# DualUSB3_0_CON.net
KiCad netlist of a schematic drawn in Altium Designer
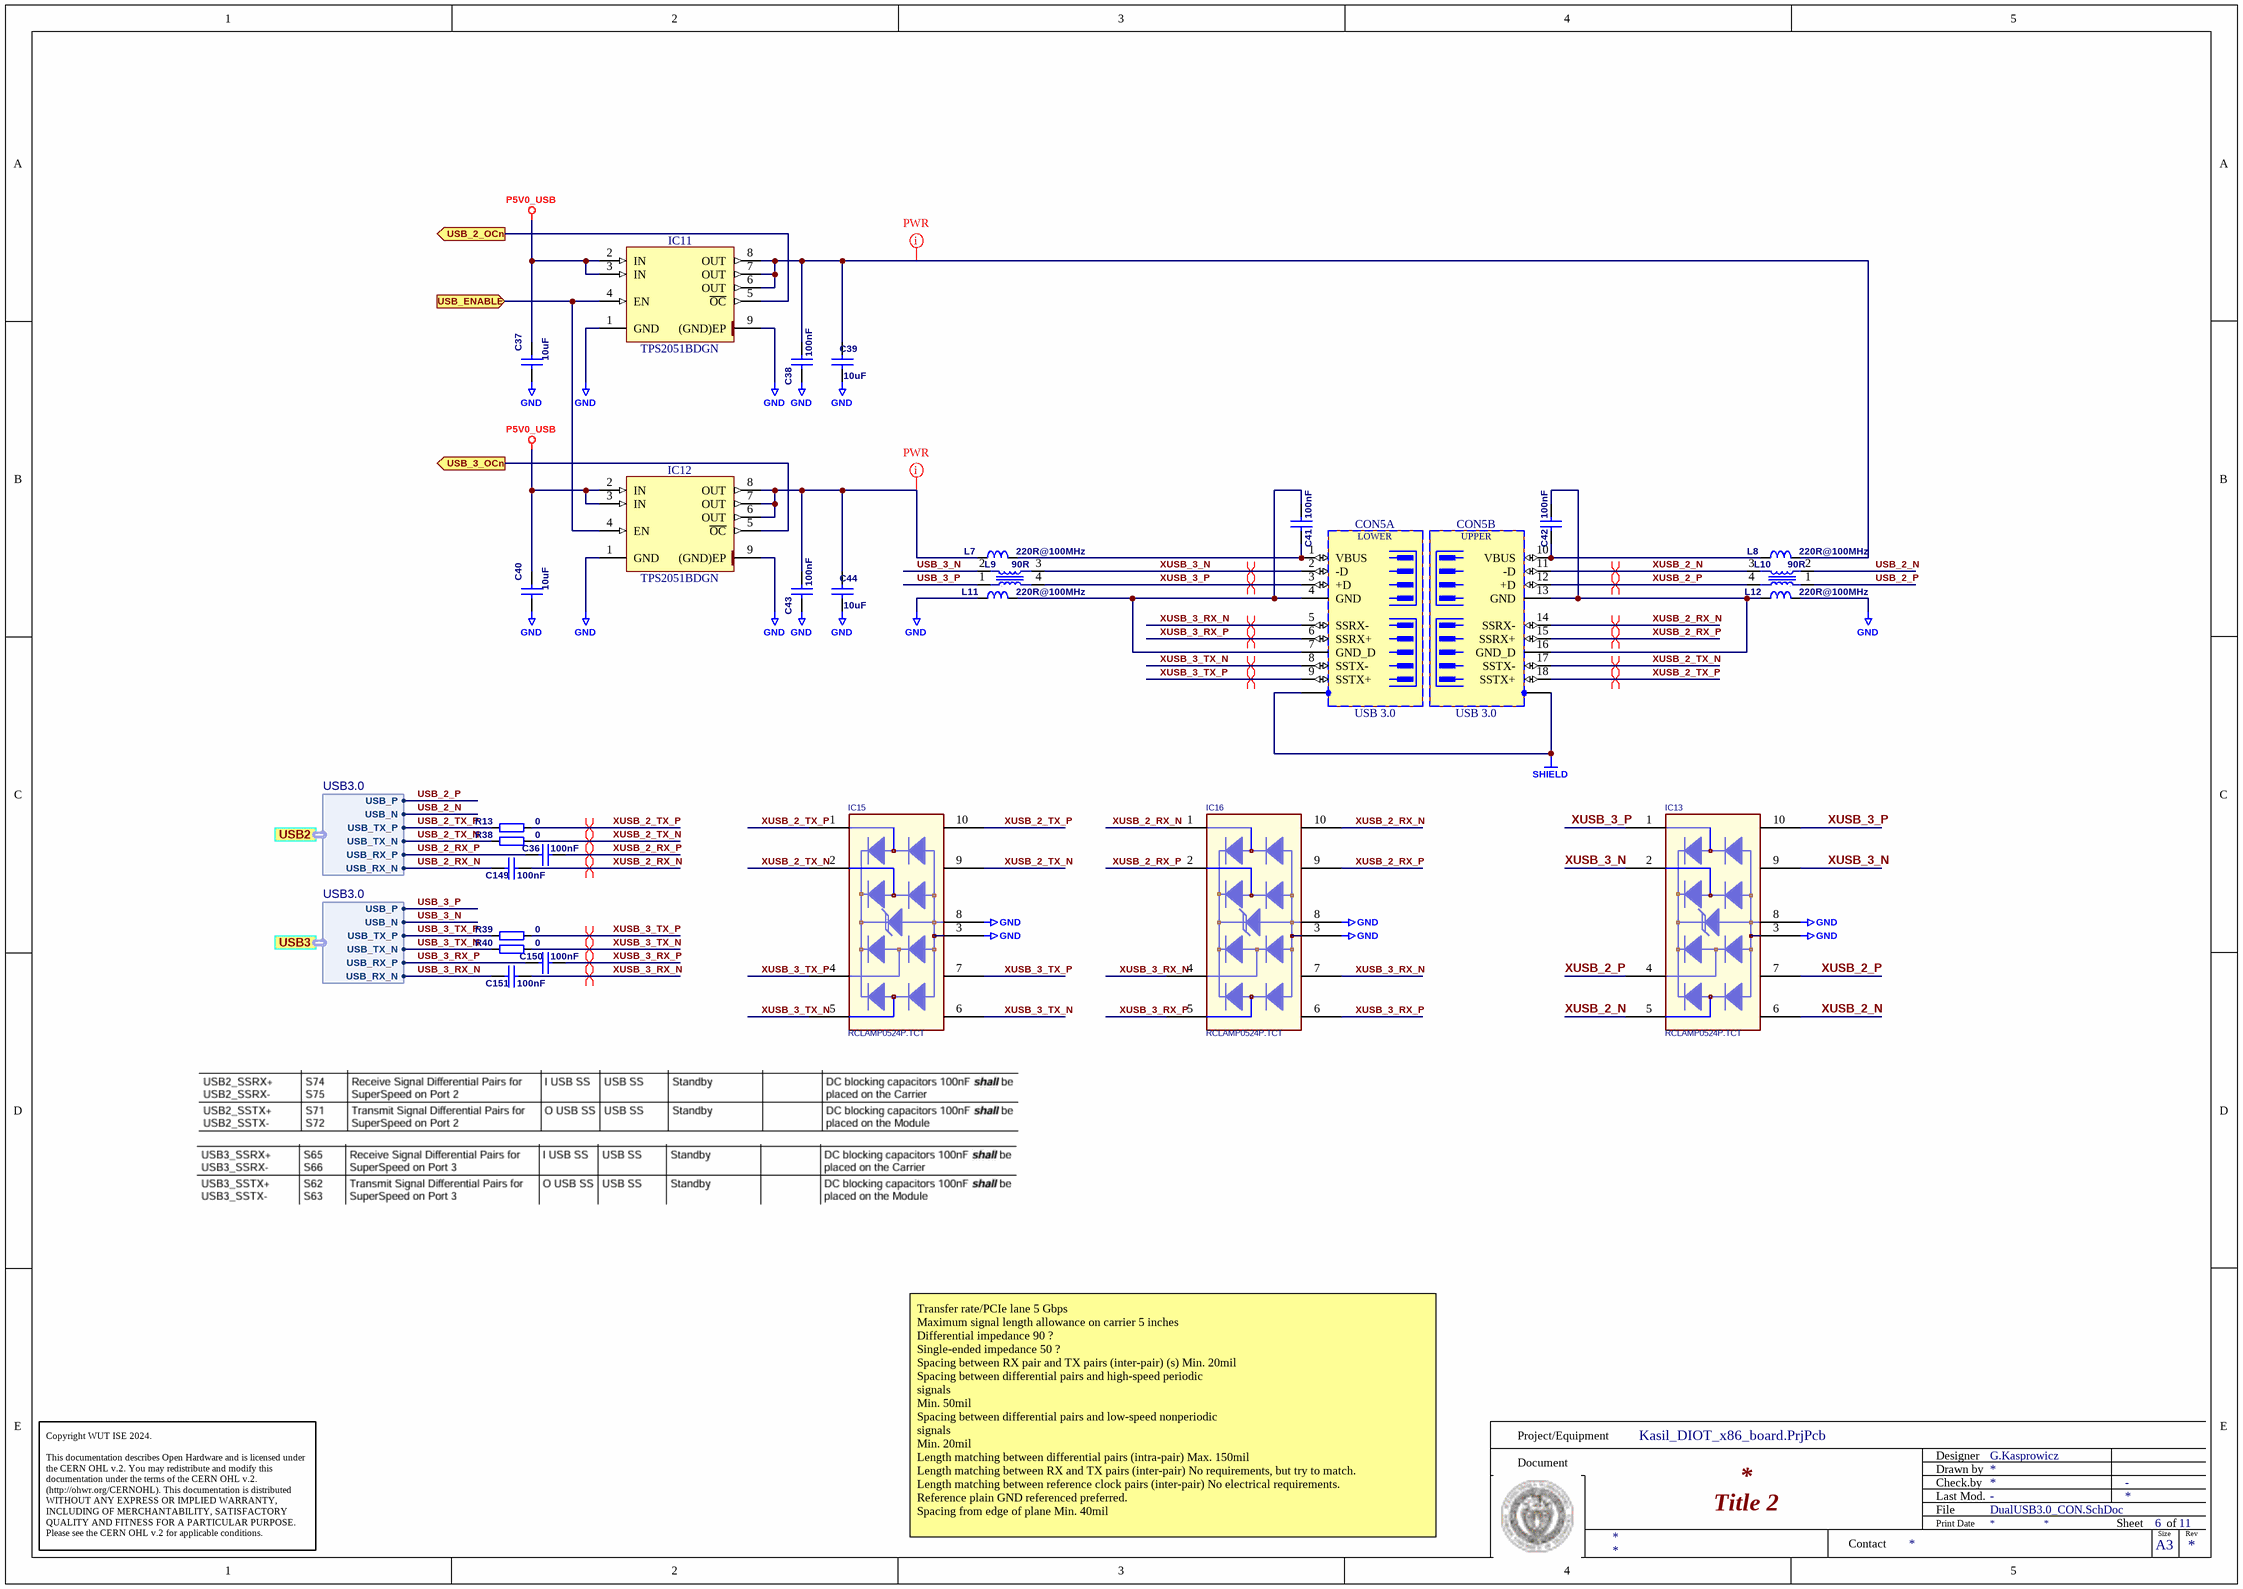
[diagram p0: DualUSB3.0_CON.SchDoc]

(export (version "E")
  (design (tool "Eeschema 10.0.6"))
  (components
    (comp (ref "C36")
      (value "100nF")
      (footprint "CAPC1005X55N")
      (description "Non-polarised capacitor")
      (fields
        (field (name "PART NUMBER") "CC0402_100NF_16V_10%_X7R")
        (field (name "VOLTAGE") "16V")
        (field (name "AUTHOR") "CERN DEM JLC")
      )
      (libsource (lib "Capacitors") (part "Capacitor - non polarized"))
    )
    (comp (ref "C37")
      (value "10uF")
      (footprint "CAPC2012X135N")
      (description "Non-polarised capacitor")
      (fields
        (field (name "PART NUMBER") "CC0805_10UF_10V_10%_X7R")
        (field (name "VOLTAGE") "10V")
        (field (name "AUTHOR") "CERN DEM JLC")
      )
      (libsource (lib "Capacitors") (part "Capacitor - non polarized"))
    )
    (comp (ref "C38")
      (value "100nF")
      (footprint "CAPC1005X55N")
      (description "Non-polarised capacitor")
      (fields
        (field (name "PART NUMBER") "CC0402_100NF_16V_10%_X7R")
        (field (name "VOLTAGE") "16V")
        (field (name "AUTHOR") "CERN DEM JLC")
      )
      (libsource (lib "Capacitors") (part "Capacitor - non polarized"))
    )
    (comp (ref "C39")
      (value "10uF")
      (footprint "CAPC2012X135N")
      (description "Non-polarised capacitor")
      (fields
        (field (name "PART NUMBER") "CC0805_10UF_10V_10%_X7R")
        (field (name "VOLTAGE") "10V")
        (field (name "AUTHOR") "CERN DEM JLC")
      )
      (libsource (lib "Capacitors") (part "Capacitor - non polarized"))
    )
    (comp (ref "C40")
      (value "10uF")
      (footprint "CAPC2012X135N")
      (description "Non-polarised capacitor")
      (fields
        (field (name "PART NUMBER") "CC0805_10UF_10V_10%_X7R")
        (field (name "VOLTAGE") "10V")
        (field (name "AUTHOR") "CERN DEM JLC")
      )
      (libsource (lib "Capacitors") (part "Capacitor - non polarized"))
    )
    (comp (ref "C41")
      (value "100nF")
      (footprint "CAPC1005X55N")
      (description "Non-polarised capacitor")
      (fields
        (field (name "PART NUMBER") "CC0402_100NF_16V_10%_X7R")
        (field (name "VOLTAGE") "16V")
        (field (name "AUTHOR") "CERN DEM JLC")
      )
      (libsource (lib "Capacitors") (part "Capacitor - non polarized"))
    )
    (comp (ref "C42")
      (value "100nF")
      (footprint "CAPC1005X55N")
      (description "Non-polarised capacitor")
      (fields
        (field (name "PART NUMBER") "CC0402_100NF_16V_10%_X7R")
        (field (name "VOLTAGE") "16V")
        (field (name "AUTHOR") "CERN DEM JLC")
      )
      (libsource (lib "Capacitors") (part "Capacitor - non polarized"))
    )
    (comp (ref "C43")
      (value "100nF")
      (footprint "CAPC1005X55N")
      (description "Non-polarised capacitor")
      (fields
        (field (name "PART NUMBER") "CC0402_100NF_16V_10%_X7R")
        (field (name "VOLTAGE") "16V")
        (field (name "AUTHOR") "CERN DEM JLC")
      )
      (libsource (lib "Capacitors") (part "Capacitor - non polarized"))
    )
    (comp (ref "C44")
      (value "10uF")
      (footprint "CAPC2012X135N")
      (description "Non-polarised capacitor")
      (fields
        (field (name "PART NUMBER") "CC0805_10UF_10V_10%_X7R")
        (field (name "VOLTAGE") "10V")
        (field (name "AUTHOR") "CERN DEM JLC")
      )
      (libsource (lib "Capacitors") (part "Capacitor - non polarized"))
    )
    (comp (ref "C149")
      (value "100nF")
      (footprint "CAPC1005X55N")
      (description "Non-polarised capacitor")
      (fields
        (field (name "PART NUMBER") "CC0402_100NF_16V_10%_X7R")
        (field (name "VOLTAGE") "16V")
        (field (name "AUTHOR") "CERN DEM JLC")
      )
      (libsource (lib "Capacitors") (part "Capacitor - non polarized"))
    )
    (comp (ref "C150")
      (value "100nF")
      (footprint "CAPC1005X55N")
      (description "Non-polarised capacitor")
      (fields
        (field (name "PART NUMBER") "CC0402_100NF_16V_10%_X7R")
        (field (name "VOLTAGE") "16V")
        (field (name "AUTHOR") "CERN DEM JLC")
      )
      (libsource (lib "Capacitors") (part "Capacitor - non polarized"))
    )
    (comp (ref "C151")
      (value "100nF")
      (footprint "CAPC1005X55N")
      (description "Non-polarised capacitor")
      (fields
        (field (name "PART NUMBER") "CC0402_100NF_16V_10%_X7R")
        (field (name "VOLTAGE") "16V")
        (field (name "AUTHOR") "CERN DEM JLC")
      )
      (libsource (lib "Capacitors") (part "Capacitor - non polarized"))
    )
    (comp (ref "CON5")
      (value "USB 3.0")
      (footprint "WURTH_692141030100")
      (description "2x9 Pin + 1 Shield  Duals USB 3.0 Type A Receptacle")
      (fields
        (field (name "PART NUMBER") "WURTH_692141030100")
        (field (name "MANUFACTURER") "WURTH ELEKTRONIK")
        (field (name "AUTHOR") "CERN DEM JLC")
      )
      (libsource (lib "") (part "Connector USB3 x2 Type A - 18 Pin + 1 Shield_1"))
    )
    (comp (ref "IC11")
      (value "TPS2051BDGN")
      (footprint "SOP65P490X110-9N-R157X189")
      (description "One Channel, Current-Limited, Power-Distribution Switches")
      (fields (field (name "MANUFACTURER") "TEXAS INSTRUMENTS") (field (name "AUTHOR") "CERN DEM BC"))
      (libsource (lib "ICs And Semiconductors") (part "TPS2051BDGN"))
    )
    (comp (ref "IC12")
      (value "TPS2051BDGN")
      (footprint "SOP65P490X110-9N-R157X189")
      (description "One Channel, Current-Limited, Power-Distribution Switches")
      (fields (field (name "MANUFACTURER") "TEXAS INSTRUMENTS") (field (name "AUTHOR") "CERN DEM BC"))
      (libsource (lib "ICs And Semiconductors") (part "TPS2051BDGN"))
    )
    (comp (ref "IC13")
      (value "RCLAMP0524P.TCT")
      (description "DIODE,RCLAMP0524P,SEMTECH")
      (libsource (lib "LIBRARY_SCH") (part "D_TVS_RCLAMP0524P"))
    )
    (comp (ref "IC15")
      (value "RCLAMP0524P.TCT")
      (description "DIODE,RCLAMP0524P,SEMTECH")
      (libsource (lib "LIBRARY_SCH") (part "D_TVS_RCLAMP0524P"))
    )
    (comp (ref "IC16")
      (value "RCLAMP0524P.TCT")
      (description "DIODE,RCLAMP0524P,SEMTECH")
      (libsource (lib "LIBRARY_SCH") (part "D_TVS_RCLAMP0524P"))
    )
    (comp (ref "L7")
      (value "220R@100MHz")
      (footprint "INDC2012X105N")
      (description "Inductor")
      (fields
        (field (name "PART NUMBER") "IND0805_MURATA_BLM21PG221SN1D")
        (field (name "POWER") "2A")
        (field (name "AUTHOR") "CERN DEM JLC")
      )
      (libsource (lib "Inductors & Transformers") (part "Inductor"))
    )
    (comp (ref "L8")
      (value "220R@100MHz")
      (footprint "INDC2012X105N")
      (description "Inductor")
      (fields
        (field (name "PART NUMBER") "IND0805_MURATA_BLM21PG221SN1D")
        (field (name "POWER") "2A")
        (field (name "AUTHOR") "CERN DEM JLC")
      )
      (libsource (lib "Inductors & Transformers") (part "Inductor"))
    )
    (comp (ref "L9")
      (value "90R")
      (footprint "DLSCM0805")
      (description "Common Mode Choke 90R")
      (fields (field (name "Comment") "DLSCM0805-900M or DLW21SN900SQ2L"))
      (libsource (lib "") (part "L_CMC_DLSCM0805_90R_1"))
    )
    (comp (ref "L10")
      (value "90R")
      (footprint "DLSCM0805")
      (description "Common Mode Choke 90R")
      (fields (field (name "Comment") "DLSCM0805-900M or DLW21SN900SQ2L"))
      (libsource (lib "LIBRARY_SCH") (part "L_CMC_DLSCM0805_90R"))
    )
    (comp (ref "L11")
      (value "220R@100MHz")
      (footprint "INDC2012X105N")
      (description "Inductor")
      (fields
        (field (name "PART NUMBER") "IND0805_MURATA_BLM21PG221SN1D")
        (field (name "POWER") "2A")
        (field (name "AUTHOR") "CERN DEM JLC")
      )
      (libsource (lib "Inductors & Transformers") (part "Inductor"))
    )
    (comp (ref "L12")
      (value "220R@100MHz")
      (footprint "INDC2012X105N")
      (description "Inductor")
      (fields
        (field (name "PART NUMBER") "IND0805_MURATA_BLM21PG221SN1D")
        (field (name "POWER") "2A")
        (field (name "AUTHOR") "CERN DEM JLC")
      )
      (libsource (lib "Inductors & Transformers") (part "Inductor"))
    )
    (comp (ref "R13")
      (value "0")
      (footprint "RESC1005X40N")
      (description "Resistor")
      (fields
        (field (name "PART NUMBER") "R0402_0R_JUMPER")
        (field (name "MANUFACTURER") "GENERIC")
        (field (name "AUTHOR") "CERN DEM JLC")
      )
      (libsource (lib "Resistors") (part "Resistor"))
    )
    (comp (ref "R38")
      (value "0")
      (footprint "RESC1005X40N")
      (description "Resistor")
      (fields
        (field (name "PART NUMBER") "R0402_0R_JUMPER")
        (field (name "MANUFACTURER") "GENERIC")
        (field (name "AUTHOR") "CERN DEM JLC")
      )
      (libsource (lib "Resistors") (part "Resistor"))
    )
    (comp (ref "R39")
      (value "0")
      (footprint "RESC1005X40N")
      (description "Resistor")
      (fields
        (field (name "PART NUMBER") "R0402_0R_JUMPER")
        (field (name "MANUFACTURER") "GENERIC")
        (field (name "AUTHOR") "CERN DEM JLC")
      )
      (libsource (lib "Resistors") (part "Resistor"))
    )
    (comp (ref "R40")
      (value "0")
      (footprint "RESC1005X40N")
      (description "Resistor")
      (fields
        (field (name "PART NUMBER") "R0402_0R_JUMPER")
        (field (name "MANUFACTURER") "GENERIC")
        (field (name "AUTHOR") "CERN DEM JLC")
      )
      (libsource (lib "Resistors") (part "Resistor"))
    )
  )
  (nets
    (net (code "2") (name "/USB_2_N") (class "Default")
      (node (ref "L10") (pin "2") (pinfunction "2_2") (pintype "passive"))
    )
    (net (code "3") (name "/USB_2_OCn") (class "Default")
      (node (ref "IC11") (pin "5") (pinfunction "~{OC}_5") (pintype "output"))
    )
    (net (code "4") (name "/USB_2_P") (class "Default")
      (node (ref "L10") (pin "1") (pinfunction "1_1") (pintype "passive"))
    )
    (net (code "5") (name "/USB_2_RX_N") (class "Default")
      (node (ref "C149") (pin "1") (pinfunction "1_1") (pintype "passive"))
    )
    (net (code "6") (name "/USB_2_RX_P") (class "Default")
      (node (ref "C36") (pin "1") (pinfunction "1_1") (pintype "passive"))
    )
    (net (code "7") (name "/USB_2_TX_N") (class "Default")
      (node (ref "R38") (pin "1") (pinfunction "1_1") (pintype "passive"))
    )
    (net (code "8") (name "/USB_2_TX_P") (class "Default")
      (node (ref "R13") (pin "1") (pinfunction "1_1") (pintype "passive"))
    )
    (net (code "9") (name "/USB_3_N") (class "Default")
      (node (ref "L9") (pin "2") (pinfunction "2_2") (pintype "passive"))
    )
    (net (code "10") (name "/USB_3_OCn") (class "Default")
      (node (ref "IC12") (pin "5") (pinfunction "~{OC}_5") (pintype "output"))
    )
    (net (code "11") (name "/USB_3_P") (class "Default")
      (node (ref "L9") (pin "1") (pinfunction "1_1") (pintype "passive"))
    )
    (net (code "12") (name "/USB_3_RX_N") (class "Default")
      (node (ref "C151") (pin "1") (pinfunction "1_1") (pintype "passive"))
    )
    (net (code "13") (name "/USB_3_RX_P") (class "Default")
      (node (ref "C150") (pin "1") (pinfunction "1_1") (pintype "passive"))
    )
    (net (code "14") (name "/USB_3_TX_N") (class "Default")
      (node (ref "R40") (pin "1") (pinfunction "1_1") (pintype "passive"))
    )
    (net (code "15") (name "/USB_3_TX_P") (class "Default")
      (node (ref "R39") (pin "1") (pinfunction "1_1") (pintype "passive"))
    )
    (net (code "16") (name "/USB_ENABLE") (class "Default")
      (node (ref "IC11") (pin "4") (pinfunction "EN_4") (pintype "input"))
      (node (ref "IC12") (pin "4") (pinfunction "EN_4") (pintype "input"))
    )
    (net (code "17") (name "/XUSB_2_N") (class "Default")
      (node (ref "CON5") (pin "11") (pinfunction "-D_11") (pintype "bidirectional"))
      (node (ref "IC13") (pin "5") (pinfunction "5_5") (pintype "passive"))
      (node (ref "IC13") (pin "6") (pinfunction "6_6") (pintype "passive"))
      (node (ref "L10") (pin "3") (pinfunction "3_3") (pintype "passive"))
    )
    (net (code "18") (name "/XUSB_2_P") (class "Default")
      (node (ref "CON5") (pin "12") (pinfunction "+D_12") (pintype "bidirectional"))
      (node (ref "IC13") (pin "4") (pinfunction "4_4") (pintype "passive"))
      (node (ref "IC13") (pin "7") (pinfunction "7_7") (pintype "passive"))
      (node (ref "L10") (pin "4") (pinfunction "4_4") (pintype "passive"))
    )
    (net (code "19") (name "/XUSB_2_RX_N") (class "Default")
      (node (ref "C149") (pin "2") (pinfunction "2_2") (pintype "passive"))
      (node (ref "CON5") (pin "14") (pinfunction "SSRX-_14") (pintype "bidirectional"))
      (node (ref "IC16") (pin "1") (pinfunction "1_1") (pintype "passive"))
      (node (ref "IC16") (pin "10") (pinfunction "10_10") (pintype "passive"))
    )
    (net (code "20") (name "/XUSB_2_RX_P") (class "Default")
      (node (ref "C36") (pin "2") (pinfunction "2_2") (pintype "passive"))
      (node (ref "CON5") (pin "15") (pinfunction "SSRX+_15") (pintype "bidirectional"))
      (node (ref "IC16") (pin "2") (pinfunction "2_2") (pintype "passive"))
      (node (ref "IC16") (pin "9") (pinfunction "9_9") (pintype "passive"))
    )
    (net (code "21") (name "/XUSB_2_TX_N") (class "Default")
      (node (ref "CON5") (pin "17") (pinfunction "SSTX-_17") (pintype "bidirectional"))
      (node (ref "IC15") (pin "2") (pinfunction "2_2") (pintype "passive"))
      (node (ref "IC15") (pin "9") (pinfunction "9_9") (pintype "passive"))
      (node (ref "R38") (pin "2") (pinfunction "2_2") (pintype "passive"))
    )
    (net (code "22") (name "/XUSB_2_TX_P") (class "Default")
      (node (ref "CON5") (pin "18") (pinfunction "SSTX+_18") (pintype "bidirectional"))
      (node (ref "IC15") (pin "1") (pinfunction "1_1") (pintype "passive"))
      (node (ref "IC15") (pin "10") (pinfunction "10_10") (pintype "passive"))
      (node (ref "R13") (pin "2") (pinfunction "2_2") (pintype "passive"))
    )
    (net (code "23") (name "/XUSB_3_N") (class "Default")
      (node (ref "CON5") (pin "2") (pinfunction "-D_2") (pintype "bidirectional"))
      (node (ref "IC13") (pin "2") (pinfunction "2_2") (pintype "passive"))
      (node (ref "IC13") (pin "9") (pinfunction "9_9") (pintype "passive"))
      (node (ref "L9") (pin "3") (pinfunction "3_3") (pintype "passive"))
    )
    (net (code "24") (name "/XUSB_3_P") (class "Default")
      (node (ref "CON5") (pin "3") (pinfunction "+D_3") (pintype "bidirectional"))
      (node (ref "IC13") (pin "1") (pinfunction "1_1") (pintype "passive"))
      (node (ref "IC13") (pin "10") (pinfunction "10_10") (pintype "passive"))
      (node (ref "L9") (pin "4") (pinfunction "4_4") (pintype "passive"))
    )
    (net (code "25") (name "/XUSB_3_RX_N") (class "Default")
      (node (ref "C151") (pin "2") (pinfunction "2_2") (pintype "passive"))
      (node (ref "CON5") (pin "5") (pinfunction "SSRX-_5") (pintype "bidirectional"))
      (node (ref "IC16") (pin "4") (pinfunction "4_4") (pintype "passive"))
      (node (ref "IC16") (pin "7") (pinfunction "7_7") (pintype "passive"))
    )
    (net (code "26") (name "/XUSB_3_RX_P") (class "Default")
      (node (ref "C150") (pin "2") (pinfunction "2_2") (pintype "passive"))
      (node (ref "CON5") (pin "6") (pinfunction "SSRX+_6") (pintype "bidirectional"))
      (node (ref "IC16") (pin "5") (pinfunction "5_5") (pintype "passive"))
      (node (ref "IC16") (pin "6") (pinfunction "6_6") (pintype "passive"))
    )
    (net (code "27") (name "/XUSB_3_TX_N") (class "Default")
      (node (ref "CON5") (pin "8") (pinfunction "SSTX-_8") (pintype "bidirectional"))
      (node (ref "IC15") (pin "5") (pinfunction "5_5") (pintype "passive"))
      (node (ref "IC15") (pin "6") (pinfunction "6_6") (pintype "passive"))
      (node (ref "R40") (pin "2") (pinfunction "2_2") (pintype "passive"))
    )
    (net (code "28") (name "/XUSB_3_TX_P") (class "Default")
      (node (ref "CON5") (pin "9") (pinfunction "SSTX+_9") (pintype "bidirectional"))
      (node (ref "IC15") (pin "4") (pinfunction "4_4") (pintype "passive"))
      (node (ref "IC15") (pin "7") (pinfunction "7_7") (pintype "passive"))
      (node (ref "R39") (pin "2") (pinfunction "2_2") (pintype "passive"))
    )
    (net (code "30") (name "GND") (class "Default")
      (node (ref "C37") (pin "1") (pinfunction "1_1") (pintype "passive"))
      (node (ref "C38") (pin "1") (pinfunction "1_1") (pintype "passive"))
      (node (ref "C39") (pin "1") (pinfunction "1_1") (pintype "passive"))
      (node (ref "C40") (pin "1") (pinfunction "1_1") (pintype "passive"))
      (node (ref "C43") (pin "1") (pinfunction "1_1") (pintype "passive"))
      (node (ref "C44") (pin "1") (pinfunction "1_1") (pintype "passive"))
      (node (ref "IC11") (pin "1") (pinfunction "GND_1") (pintype "power_in"))
      (node (ref "IC11") (pin "9") (pinfunction "(GND)EP_9") (pintype "power_in"))
      (node (ref "IC12") (pin "1") (pinfunction "GND_1") (pintype "power_in"))
      (node (ref "IC12") (pin "9") (pinfunction "(GND)EP_9") (pintype "power_in"))
      (node (ref "IC13") (pin "3") (pinfunction "3_3") (pintype "passive"))
      (node (ref "IC13") (pin "8") (pinfunction "8_8") (pintype "passive"))
      (node (ref "IC15") (pin "3") (pinfunction "3_3") (pintype "passive"))
      (node (ref "IC15") (pin "8") (pinfunction "8_8") (pintype "passive"))
      (node (ref "IC16") (pin "3") (pinfunction "3_3") (pintype "passive"))
      (node (ref "IC16") (pin "8") (pinfunction "8_8") (pintype "passive"))
      (node (ref "L11") (pin "1") (pinfunction "1_1") (pintype "passive"))
      (node (ref "L12") (pin "2") (pinfunction "2_2") (pintype "passive"))
    )
    (net (code "31") (name "Net-(C38-Pad2)") (class "Default")
      (node (ref "C38") (pin "2") (pinfunction "2_2") (pintype "passive"))
      (node (ref "C39") (pin "2") (pinfunction "2_2") (pintype "passive"))
      (node (ref "IC11") (pin "6") (pinfunction "OUT_6") (pintype "output"))
      (node (ref "IC11") (pin "7") (pinfunction "OUT_7") (pintype "output"))
      (node (ref "IC11") (pin "8") (pinfunction "OUT_8") (pintype "output"))
      (node (ref "L8") (pin "2") (pinfunction "2_2") (pintype "passive"))
    )
    (net (code "32") (name "Net-(C43-Pad2)") (class "Default")
      (node (ref "C43") (pin "2") (pinfunction "2_2") (pintype "passive"))
      (node (ref "C44") (pin "2") (pinfunction "2_2") (pintype "passive"))
      (node (ref "IC12") (pin "6") (pinfunction "OUT_6") (pintype "output"))
      (node (ref "IC12") (pin "7") (pinfunction "OUT_7") (pintype "output"))
      (node (ref "IC12") (pin "8") (pinfunction "OUT_8") (pintype "output"))
      (node (ref "L7") (pin "1") (pinfunction "1_1") (pintype "passive"))
    )
    (net (code "33") (name "Net-(CON5A-GND)") (class "Default")
      (node (ref "C41") (pin "2") (pinfunction "2_2") (pintype "passive"))
      (node (ref "CON5") (pin "4") (pinfunction "GND_4") (pintype "power_in"))
      (node (ref "CON5") (pin "7") (pinfunction "GND_D_7") (pintype "power_in"))
      (node (ref "L11") (pin "2") (pinfunction "2_2") (pintype "passive"))
    )
    (net (code "34") (name "Net-(CON5A-VBUS)") (class "Default")
      (node (ref "C41") (pin "1") (pinfunction "1_1") (pintype "passive"))
      (node (ref "CON5") (pin "1") (pinfunction "VBUS_1") (pintype "bidirectional"))
      (node (ref "L7") (pin "2") (pinfunction "2_2") (pintype "passive"))
    )
    (net (code "35") (name "Net-(CON5B-GND)") (class "Default")
      (node (ref "C42") (pin "2") (pinfunction "2_2") (pintype "passive"))
      (node (ref "CON5") (pin "13") (pinfunction "GND_13") (pintype "power_in"))
      (node (ref "CON5") (pin "16") (pinfunction "GND_D_16") (pintype "power_in"))
      (node (ref "L12") (pin "1") (pinfunction "1_1") (pintype "passive"))
    )
    (net (code "36") (name "Net-(CON5B-VBUS)") (class "Default")
      (node (ref "C42") (pin "1") (pinfunction "1_1") (pintype "passive"))
      (node (ref "CON5") (pin "10") (pinfunction "VBUS_10") (pintype "bidirectional"))
      (node (ref "L8") (pin "1") (pinfunction "1_1") (pintype "passive"))
    )
    (net (code "37") (name "P5V0_USB") (class "Default")
      (node (ref "C37") (pin "2") (pinfunction "2_2") (pintype "passive"))
      (node (ref "C40") (pin "2") (pinfunction "2_2") (pintype "passive"))
      (node (ref "IC11") (pin "2") (pinfunction "IN_2") (pintype "input"))
      (node (ref "IC11") (pin "3") (pinfunction "IN_3") (pintype "input"))
      (node (ref "IC12") (pin "2") (pinfunction "IN_2") (pintype "input"))
      (node (ref "IC12") (pin "3") (pinfunction "IN_3") (pintype "input"))
    )
    (net (code "38") (name "SHIELD") (class "Default")
      (node (ref "CON5") (pin "19") (pinfunction "SHIELD_19") (pintype "power_in"))
      (node (ref "CON5") (pin "20") (pinfunction "SHIELD_20") (pintype "power_in"))
    )
  )
)
